# chimera.net
KiCad netlist of a schematic drawn in EAGLE
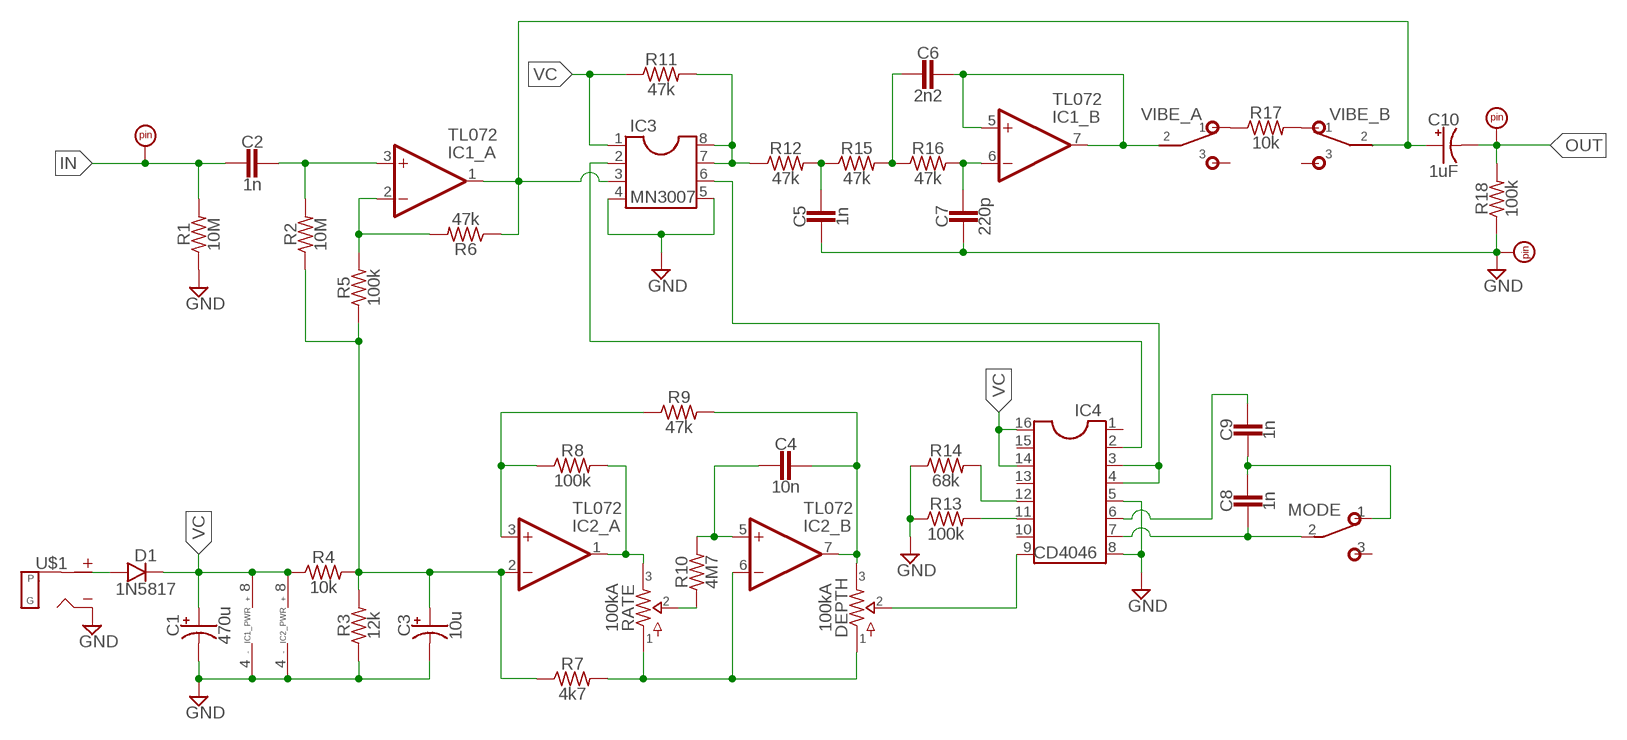
[diagram p0: schematic, sheet 1]

(export (version "E")
  (design (tool "Eeschema 10.0.6"))
  (components
    (comp (ref "C1")
      (value "470u")
      (footprint "eagle-import:080_035")
      (libsource (lib "eagle-import") (part "0801"))
    )
    (comp (ref "C2")
      (value "1n")
      (footprint "eagle-import:050X030_025_2")
      (libsource (lib "eagle-import") (part "CER/FILM2"))
    )
    (comp (ref "C3")
      (value "10u")
      (footprint "eagle-import:050_020_1")
      (libsource (lib "eagle-import") (part "0501"))
    )
    (comp (ref "C4")
      (value "10n")
      (footprint "eagle-import:BOX_MED")
      (libsource (lib "eagle-import") (part "CER/FILMBOX.2"))
    )
    (comp (ref "C5")
      (value "1n")
      (footprint "eagle-import:050X030_025_2")
      (libsource (lib "eagle-import") (part "CER/FILM2"))
    )
    (comp (ref "C6")
      (value "2n2")
      (footprint "eagle-import:050X030_025_2")
      (libsource (lib "eagle-import") (part "CER/FILM2"))
    )
    (comp (ref "C7")
      (value "220p")
      (footprint "eagle-import:050X030_025_2")
      (libsource (lib "eagle-import") (part "CER/FILM2"))
    )
    (comp (ref "C8")
      (value "1n")
      (footprint "eagle-import:050X030_025_2")
      (libsource (lib "eagle-import") (part "CER/FILM2"))
    )
    (comp (ref "C9")
      (value "1n")
      (footprint "eagle-import:050X030_025_2")
      (libsource (lib "eagle-import") (part "CER/FILM2"))
    )
    (comp (ref "C10")
      (value "1uF")
      (footprint "eagle-import:080_035")
      (libsource (lib "eagle-import") (part "0801"))
    )
    (comp (ref "D1")
      (value "1N5817")
      (footprint "eagle-import:DO41-2")
      (libsource (lib "eagle-import") (part "DO41.2"))
    )
    (comp (ref "DEPTH")
      (value "100kA")
      (footprint "eagle-import:16MM")
      (libsource (lib "eagle-import") (part "POTS16MM"))
    )
    (comp (ref "GND")
      (value "PADRND")
      (footprint "eagle-import:ROUND")
      (libsource (lib "eagle-import") (part "PADRND"))
    )
    (comp (ref "IC1")
      (value "TL072")
      (footprint "eagle-import:DIL08")
      (libsource (lib "eagle-import") (part "DUALTH"))
    )
    (comp (ref "IC2")
      (value "TL072")
      (footprint "eagle-import:DIL08")
      (libsource (lib "eagle-import") (part "DUALTH"))
    )
    (comp (ref "IC3")
      (value "MN3007")
      (footprint "eagle-import:DIL08")
      (libsource (lib "eagle-import") (part "DIL8"))
    )
    (comp (ref "IC4")
      (value "CD4046")
      (footprint "eagle-import:DIL16")
      (libsource (lib "eagle-import") (part "DIL16"))
    )
    (comp (ref "IN")
      (value "PADSQR")
      (footprint "eagle-import:SQUARE")
      (libsource (lib "eagle-import") (part "PADSQR"))
    )
    (comp (ref "MODE")
      (value "SPDTPIN_MOUNT")
      (footprint "eagle-import:1MS1T1B1C0M2QE")
      (libsource (lib "eagle-import") (part "SPDTPIN_MOUNT"))
    )
    (comp (ref "OUT")
      (value "PADSQR")
      (footprint "eagle-import:SQUARE")
      (libsource (lib "eagle-import") (part "PADSQR"))
    )
    (comp (ref "R1")
      (value "10M")
      (footprint "eagle-import:R0207_3")
      (libsource (lib "eagle-import") (part "R_.3B"))
    )
    (comp (ref "R2")
      (value "10M")
      (footprint "eagle-import:R0207_3")
      (libsource (lib "eagle-import") (part "R_.3B"))
    )
    (comp (ref "R3")
      (value "12k")
      (footprint "eagle-import:R0207_3")
      (libsource (lib "eagle-import") (part "R_.3B"))
    )
    (comp (ref "R4")
      (value "10k")
      (footprint "eagle-import:R0207_3")
      (libsource (lib "eagle-import") (part "R_.3B"))
    )
    (comp (ref "R5")
      (value "100k")
      (footprint "eagle-import:R0207_3")
      (libsource (lib "eagle-import") (part "R_.3B"))
    )
    (comp (ref "R6")
      (value "47k")
      (footprint "eagle-import:R0207_3")
      (libsource (lib "eagle-import") (part "R_.3B"))
    )
    (comp (ref "R7")
      (value "4k7")
      (footprint "eagle-import:R0207_3")
      (libsource (lib "eagle-import") (part "R_.3B"))
    )
    (comp (ref "R8")
      (value "100k")
      (footprint "eagle-import:R0207_3")
      (libsource (lib "eagle-import") (part "R_.3B"))
    )
    (comp (ref "R9")
      (value "47k")
      (footprint "eagle-import:R0207_3")
      (libsource (lib "eagle-import") (part "R_.3B"))
    )
    (comp (ref "R10")
      (value "4M7")
      (footprint "eagle-import:R0207_3")
      (libsource (lib "eagle-import") (part "R_.3B"))
    )
    (comp (ref "R11")
      (value "47k")
      (footprint "eagle-import:R0207_3")
      (libsource (lib "eagle-import") (part "R_.3B"))
    )
    (comp (ref "R12")
      (value "47k")
      (footprint "eagle-import:R0207_3")
      (libsource (lib "eagle-import") (part "R_.3B"))
    )
    (comp (ref "R13")
      (value "100k")
      (footprint "eagle-import:R0207_3")
      (libsource (lib "eagle-import") (part "R_.3B"))
    )
    (comp (ref "R14")
      (value "68k")
      (footprint "eagle-import:R0207_3")
      (libsource (lib "eagle-import") (part "R_.3B"))
    )
    (comp (ref "R15")
      (value "47k")
      (footprint "eagle-import:R0207_3")
      (libsource (lib "eagle-import") (part "R_.3B"))
    )
    (comp (ref "R16")
      (value "47k")
      (footprint "eagle-import:R0207_3")
      (libsource (lib "eagle-import") (part "R_.3B"))
    )
    (comp (ref "R17")
      (value "10k")
      (footprint "eagle-import:R0207_3")
      (libsource (lib "eagle-import") (part "R_.3B"))
    )
    (comp (ref "R18")
      (value "100k")
      (footprint "eagle-import:R0207_3")
      (libsource (lib "eagle-import") (part "R_.3B"))
    )
    (comp (ref "RATE")
      (value "100kA")
      (footprint "eagle-import:16MM")
      (libsource (lib "eagle-import") (part "POTS16MM"))
    )
    (comp (ref "U$1")
      (value "DC_MONO")
      (footprint "eagle-import:DC")
      (libsource (lib "eagle-import") (part "DC_MONO"))
    )
    (comp (ref "VIBE")
      (value "DPDTTAIWAY1MD")
      (footprint "eagle-import:TAIWAY1MD")
      (libsource (lib "eagle-import") (part "DPDTTAIWAY1MD"))
    )
  )
  (nets
    (net (code "1") (name "GND") (class "Default")
      (node (ref "C1") (pin "-") (pinfunction "-_-") (pintype "passive"))
      (node (ref "C3") (pin "-") (pinfunction "-_-") (pintype "passive"))
      (node (ref "C5") (pin "1") (pinfunction "1_1") (pintype "passive"))
      (node (ref "C7") (pin "2") (pinfunction "2_2") (pintype "passive"))
      (node (ref "GND") (pin "1") (pinfunction "P$1_1") (pintype "bidirectional"))
      (node (ref "IC1") (pin "4") (pinfunction "V-_4") (pintype "power_in"))
      (node (ref "IC2") (pin "4") (pinfunction "V-_4") (pintype "power_in"))
      (node (ref "IC3") (pin "4") (pinfunction "4_4") (pintype "passive"))
      (node (ref "IC3") (pin "5") (pinfunction "5_5") (pintype "passive"))
      (node (ref "IC4") (pin "5") (pinfunction "5_5") (pintype "passive"))
      (node (ref "IC4") (pin "8") (pinfunction "8_8") (pintype "passive"))
      (node (ref "R1") (pin "1") (pinfunction "1_1") (pintype "passive"))
      (node (ref "R13") (pin "1") (pinfunction "1_1") (pintype "passive"))
      (node (ref "R14") (pin "1") (pinfunction "1_1") (pintype "passive"))
      (node (ref "R18") (pin "1") (pinfunction "1_1") (pintype "passive"))
      (node (ref "R3") (pin "1") (pinfunction "1_1") (pintype "passive"))
      (node (ref "U$1") (pin "S") (pinfunction "SLEEVE_S") (pintype "passive"))
    )
    (net (code "2") (name "IN") (class "Default")
      (node (ref "C2") (pin "1") (pinfunction "1_1") (pintype "passive"))
      (node (ref "IN") (pin "1") (pinfunction "P$1_1") (pintype "bidirectional"))
      (node (ref "R1") (pin "2") (pinfunction "2_2") (pintype "passive"))
    )
    (net (code "3") (name "Net-(C5-Pad2)") (class "Default")
      (node (ref "C5") (pin "2") (pinfunction "2_2") (pintype "passive"))
      (node (ref "R12") (pin "2") (pinfunction "2_2") (pintype "passive"))
      (node (ref "R15") (pin "1") (pinfunction "1_1") (pintype "passive"))
    )
    (net (code "4") (name "Net-(C6-Pad2)") (class "Default")
      (node (ref "C6") (pin "2") (pinfunction "2_2") (pintype "passive"))
      (node (ref "R15") (pin "2") (pinfunction "2_2") (pintype "passive"))
      (node (ref "R16") (pin "1") (pinfunction "1_1") (pintype "passive"))
    )
    (net (code "5") (name "Net-(C9-Pad2)") (class "Default")
      (node (ref "C9") (pin "2") (pinfunction "2_2") (pintype "passive"))
      (node (ref "IC4") (pin "6") (pinfunction "6_6") (pintype "passive"))
    )
    (net (code "6") (name "Net-(DEPTH-Pad2)") (class "Default")
      (node (ref "DEPTH") (pin "2") (pinfunction "2_2") (pintype "passive"))
      (node (ref "IC4") (pin "9") (pinfunction "9_9") (pintype "passive"))
    )
    (net (code "7") (name "Net-(IC1A-+IN)") (class "Default")
      (node (ref "C2") (pin "2") (pinfunction "2_2") (pintype "passive"))
      (node (ref "IC1") (pin "3") (pinfunction "+IN_3") (pintype "input"))
      (node (ref "R2") (pin "2") (pinfunction "2_2") (pintype "passive"))
    )
    (net (code "8") (name "Net-(IC1A--IN)") (class "Default")
      (node (ref "IC1") (pin "2") (pinfunction "-IN_2") (pintype "input"))
      (node (ref "R5") (pin "2") (pinfunction "2_2") (pintype "passive"))
      (node (ref "R6") (pin "2") (pinfunction "2_2") (pintype "passive"))
    )
    (net (code "9") (name "Net-(IC1A-OUT)") (class "Default")
      (node (ref "C10") (pin "+") (pinfunction "+_+") (pintype "passive"))
      (node (ref "IC1") (pin "1") (pinfunction "OUT_1") (pintype "output"))
      (node (ref "IC3") (pin "3") (pinfunction "3_3") (pintype "passive"))
      (node (ref "R6") (pin "1") (pinfunction "1_1") (pintype "passive"))
      (node (ref "VIBE") (pin "B2") (pinfunction "2_B2") (pintype "passive"))
    )
    (net (code "10") (name "Net-(IC1B-+IN)") (class "Default")
      (node (ref "C6") (pin "1") (pinfunction "1_1") (pintype "passive"))
      (node (ref "IC1") (pin "5") (pinfunction "+IN_5") (pintype "input"))
      (node (ref "IC1") (pin "7") (pinfunction "OUT_7") (pintype "output"))
      (node (ref "VIBE") (pin "A2") (pinfunction "2_A2") (pintype "passive"))
    )
    (net (code "11") (name "Net-(IC1B--IN)") (class "Default")
      (node (ref "C7") (pin "1") (pinfunction "1_1") (pintype "passive"))
      (node (ref "IC1") (pin "6") (pinfunction "-IN_6") (pintype "input"))
      (node (ref "R16") (pin "2") (pinfunction "2_2") (pintype "passive"))
    )
    (net (code "12") (name "Net-(IC2A-+IN)") (class "Default")
      (node (ref "IC2") (pin "3") (pinfunction "+IN_3") (pintype "input"))
      (node (ref "R8") (pin "1") (pinfunction "1_1") (pintype "passive"))
      (node (ref "R9") (pin "1") (pinfunction "1_1") (pintype "passive"))
    )
    (net (code "13") (name "Net-(IC2A--IN)") (class "Default")
      (node (ref "C3") (pin "+") (pinfunction "+_+") (pintype "passive"))
      (node (ref "IC2") (pin "2") (pinfunction "-IN_2") (pintype "input"))
      (node (ref "R2") (pin "1") (pinfunction "1_1") (pintype "passive"))
      (node (ref "R3") (pin "2") (pinfunction "2_2") (pintype "passive"))
      (node (ref "R4") (pin "2") (pinfunction "2_2") (pintype "passive"))
      (node (ref "R5") (pin "1") (pinfunction "1_1") (pintype "passive"))
      (node (ref "R7") (pin "1") (pinfunction "1_1") (pintype "passive"))
    )
    (net (code "14") (name "Net-(IC2A-OUT)") (class "Default")
      (node (ref "IC2") (pin "1") (pinfunction "OUT_1") (pintype "output"))
      (node (ref "R8") (pin "2") (pinfunction "2_2") (pintype "passive"))
      (node (ref "RATE") (pin "3") (pinfunction "3_3") (pintype "passive"))
    )
    (net (code "15") (name "Net-(IC2B-+IN)") (class "Default")
      (node (ref "C4") (pin "2") (pinfunction "2_2") (pintype "passive"))
      (node (ref "IC2") (pin "5") (pinfunction "+IN_5") (pintype "input"))
      (node (ref "R10") (pin "2") (pinfunction "2_2") (pintype "passive"))
    )
    (net (code "16") (name "Net-(IC2B--IN)") (class "Default")
      (node (ref "DEPTH") (pin "1") (pinfunction "1_1") (pintype "passive"))
      (node (ref "IC2") (pin "6") (pinfunction "-IN_6") (pintype "input"))
      (node (ref "R7") (pin "2") (pinfunction "2_2") (pintype "passive"))
      (node (ref "RATE") (pin "1") (pinfunction "1_1") (pintype "passive"))
    )
    (net (code "17") (name "Net-(IC2B-OUT)") (class "Default")
      (node (ref "C4") (pin "1") (pinfunction "1_1") (pintype "passive"))
      (node (ref "DEPTH") (pin "3") (pinfunction "3_3") (pintype "passive"))
      (node (ref "IC2") (pin "7") (pinfunction "OUT_7") (pintype "output"))
      (node (ref "R9") (pin "2") (pinfunction "2_2") (pintype "passive"))
    )
    (net (code "18") (name "Net-(IC3-Pad2)") (class "Default")
      (node (ref "IC3") (pin "2") (pinfunction "2_2") (pintype "passive"))
      (node (ref "IC4") (pin "2") (pinfunction "2_2") (pintype "passive"))
    )
    (net (code "19") (name "Net-(IC3-Pad6)") (class "Default")
      (node (ref "IC3") (pin "6") (pinfunction "6_6") (pintype "passive"))
      (node (ref "IC4") (pin "3") (pinfunction "3_3") (pintype "passive"))
      (node (ref "IC4") (pin "4") (pinfunction "4_4") (pintype "passive"))
    )
    (net (code "20") (name "Net-(IC3-Pad7)") (class "Default")
      (node (ref "IC3") (pin "7") (pinfunction "7_7") (pintype "passive"))
      (node (ref "IC3") (pin "8") (pinfunction "8_8") (pintype "passive"))
      (node (ref "R11") (pin "2") (pinfunction "2_2") (pintype "passive"))
      (node (ref "R12") (pin "1") (pinfunction "1_1") (pintype "passive"))
    )
    (net (code "21") (name "Net-(IC4-Pad11)") (class "Default")
      (node (ref "IC4") (pin "11") (pinfunction "11_11") (pintype "passive"))
      (node (ref "R13") (pin "2") (pinfunction "2_2") (pintype "passive"))
    )
    (net (code "22") (name "Net-(IC4-Pad12)") (class "Default")
      (node (ref "IC4") (pin "12") (pinfunction "12_12") (pintype "passive"))
      (node (ref "R14") (pin "2") (pinfunction "2_2") (pintype "passive"))
    )
    (net (code "23") (name "Net-(MODE-O)") (class "Default")
      (node (ref "C8") (pin "2") (pinfunction "2_2") (pintype "passive"))
      (node (ref "C9") (pin "1") (pinfunction "1_1") (pintype "passive"))
      (node (ref "MODE") (pin "1") (pinfunction "O_1") (pintype "passive"))
    )
    (net (code "24") (name "Net-(MODE-P)") (class "Default")
      (node (ref "C8") (pin "1") (pinfunction "1_1") (pintype "passive"))
      (node (ref "IC4") (pin "7") (pinfunction "7_7") (pintype "passive"))
      (node (ref "MODE") (pin "2") (pinfunction "P_2") (pintype "passive"))
    )
    (net (code "25") (name "Net-(R10-Pad1)") (class "Default")
      (node (ref "R10") (pin "1") (pinfunction "1_1") (pintype "passive"))
      (node (ref "RATE") (pin "2") (pinfunction "2_2") (pintype "passive"))
    )
    (net (code "26") (name "Net-(U$1-TIP)") (class "Default")
      (node (ref "D1") (pin "A") (pinfunction "A_A") (pintype "passive"))
      (node (ref "U$1") (pin "T") (pinfunction "TIP_T") (pintype "passive"))
    )
    (net (code "27") (name "Net-(VIBEA-1)") (class "Default")
      (node (ref "R17") (pin "1") (pinfunction "1_1") (pintype "passive"))
      (node (ref "VIBE") (pin "A1") (pinfunction "1_A1") (pintype "passive"))
    )
    (net (code "28") (name "Net-(VIBEB-1)") (class "Default")
      (node (ref "R17") (pin "2") (pinfunction "2_2") (pintype "passive"))
      (node (ref "VIBE") (pin "B1") (pinfunction "1_B1") (pintype "passive"))
    )
    (net (code "29") (name "OUT") (class "Default")
      (node (ref "C10") (pin "-") (pinfunction "-_-") (pintype "passive"))
      (node (ref "OUT") (pin "1") (pinfunction "P$1_1") (pintype "bidirectional"))
      (node (ref "R18") (pin "2") (pinfunction "2_2") (pintype "passive"))
    )
    (net (code "30") (name "VC") (class "Default")
      (node (ref "C1") (pin "+") (pinfunction "+_+") (pintype "passive"))
      (node (ref "D1") (pin "C") (pinfunction "C_C") (pintype "passive"))
      (node (ref "IC1") (pin "8") (pinfunction "V+_8") (pintype "power_in"))
      (node (ref "IC2") (pin "8") (pinfunction "V+_8") (pintype "power_in"))
      (node (ref "IC3") (pin "1") (pinfunction "1_1") (pintype "passive"))
      (node (ref "IC4") (pin "14") (pinfunction "14_14") (pintype "passive"))
      (node (ref "IC4") (pin "16") (pinfunction "16_16") (pintype "passive"))
      (node (ref "R11") (pin "1") (pinfunction "1_1") (pintype "passive"))
      (node (ref "R4") (pin "1") (pinfunction "1_1") (pintype "passive"))
    )
    (net (code "31") (name "unconnected-(IC4-Pad1)") (class "Default")
      (node (ref "IC4") (pin "1") (pinfunction "1_1") (pintype "passive"))
    )
    (net (code "32") (name "unconnected-(IC4-Pad10)") (class "Default")
      (node (ref "IC4") (pin "10") (pinfunction "10_10") (pintype "passive"))
    )
    (net (code "33") (name "unconnected-(IC4-Pad13)") (class "Default")
      (node (ref "IC4") (pin "13") (pinfunction "13_13") (pintype "passive"))
    )
    (net (code "34") (name "unconnected-(IC4-Pad15)") (class "Default")
      (node (ref "IC4") (pin "15") (pinfunction "15_15") (pintype "passive"))
    )
    (net (code "35") (name "unconnected-(MODE-S-Pad3)") (class "Default")
      (node (ref "MODE") (pin "3") (pinfunction "S_3") (pintype "passive"))
    )
    (net (code "36") (name "unconnected-(VIBEA-3-PadA3)") (class "Default")
      (node (ref "VIBE") (pin "A3") (pinfunction "3_A3") (pintype "passive"))
    )
    (net (code "37") (name "unconnected-(VIBEB-3-PadB3)") (class "Default")
      (node (ref "VIBE") (pin "B3") (pinfunction "3_B3") (pintype "passive"))
    )
  )
)
